# xr2206_-_FGG6.net
KiCad netlist of a schematic drawn in EAGLE
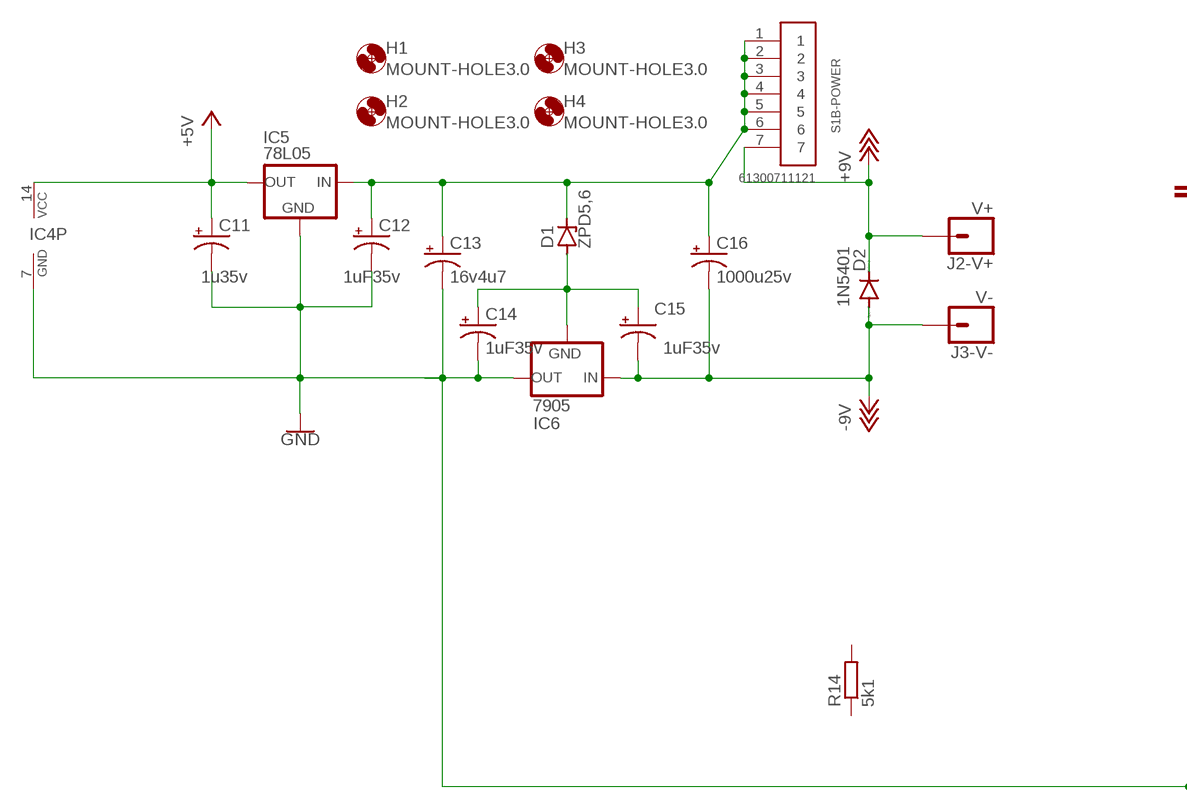
[diagram p0: schematic, sheet 1, part 1 of 2]
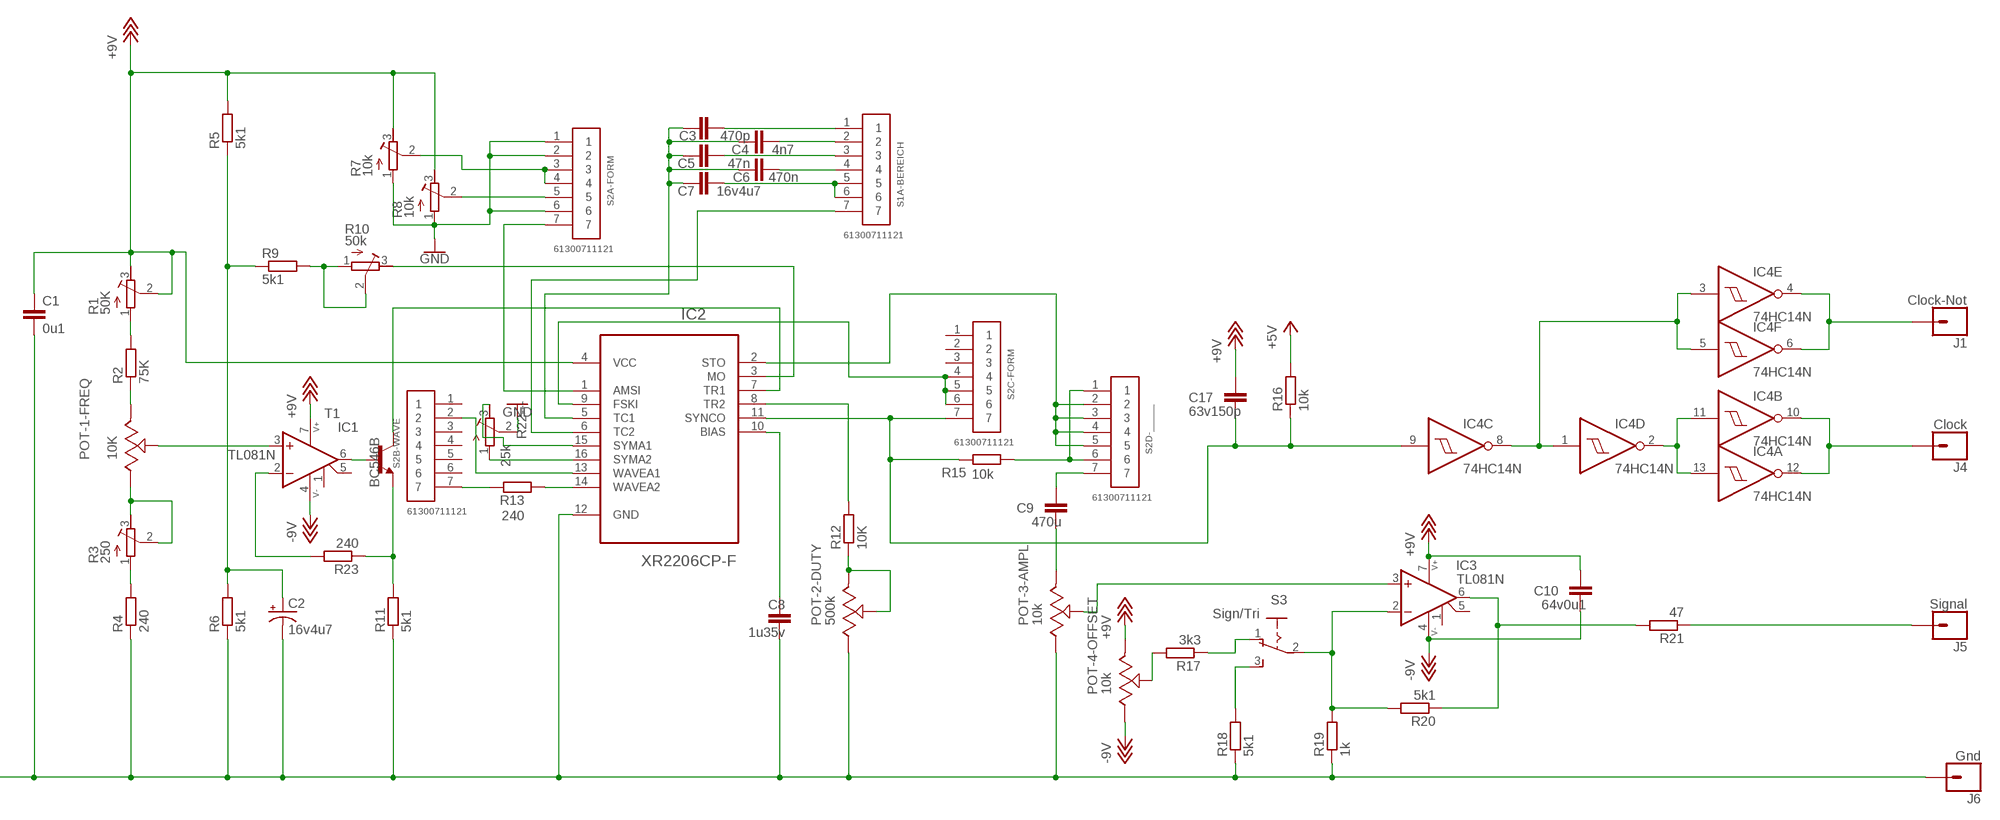
[diagram p1: schematic, sheet 1, part 2 of 2]

(export (version "E")
  (design (tool "Eeschema 10.0.6"))
  (components
    (comp (ref "C1")
      (value "0u1")
      (footprint "eagle-import:CAP-PTH-10MM")
      (libsource (lib "eagle-import") (part "10NF-PTH-10MM-10000V-1-%"))
    )
    (comp (ref "C2")
      (value "16v4u7")
      (footprint "eagle-import:CPOL-RADIAL-5MM-10MM-KIT")
      (libsource (lib "eagle-import") (part "1000UF-RADIAL-5MM-35V-20%-KIT"))
    )
    (comp (ref "C3")
      (value "470p")
      (footprint "eagle-import:CAP-PTH-10MM")
      (libsource (lib "eagle-import") (part "10NF-PTH-10MM-10000V-1-%"))
    )
    (comp (ref "C4")
      (value "4n7")
      (footprint "eagle-import:CAP-PTH-10MM")
      (libsource (lib "eagle-import") (part "10NF-PTH-10MM-10000V-1-%"))
    )
    (comp (ref "C5")
      (value "47n")
      (footprint "eagle-import:CAP-PTH-10MM")
      (libsource (lib "eagle-import") (part "10NF-PTH-10MM-10000V-1-%"))
    )
    (comp (ref "C6")
      (value "470n")
      (footprint "eagle-import:CAP-PTH-10MM")
      (libsource (lib "eagle-import") (part "10NF-PTH-10MM-10000V-1-%"))
    )
    (comp (ref "C7")
      (value "16v4u7")
      (footprint "eagle-import:CAP-PTH-10MM")
      (libsource (lib "eagle-import") (part "10NF-PTH-10MM-10000V-1-%"))
    )
    (comp (ref "C8")
      (value "1u35v")
      (footprint "eagle-import:CAP-PTH-10MM")
      (libsource (lib "eagle-import") (part "10NF-PTH-10MM-10000V-1-%"))
    )
    (comp (ref "C9")
      (value "470u")
      (footprint "eagle-import:CAP-PTH-10MM")
      (libsource (lib "eagle-import") (part "10NF-PTH-10MM-10000V-1-%"))
    )
    (comp (ref "C10")
      (value "64v0u1")
      (footprint "eagle-import:CAP-PTH-10MM")
      (libsource (lib "eagle-import") (part "10NF-PTH-10MM-10000V-1-%"))
    )
    (comp (ref "C11")
      (value "1u35v")
      (footprint "eagle-import:CPOL-RADIAL-2.5MM-5MM")
      (libsource (lib "eagle-import") (part "10UF-POLAR-RADIAL-2.5MM-25V-20%"))
    )
    (comp (ref "C12")
      (value "1uF35v")
      (footprint "eagle-import:CPOL-RADIAL-2.5MM-5MM")
      (libsource (lib "eagle-import") (part "10UF-POLAR-RADIAL-2.5MM-25V-20%"))
    )
    (comp (ref "C13")
      (value "16v4u7")
      (footprint "eagle-import:CPOL-RADIAL-2.5MM-5MM")
      (libsource (lib "eagle-import") (part "10UF-POLAR-RADIAL-2.5MM-25V-20%"))
    )
    (comp (ref "C14")
      (value "1uF35v")
      (footprint "eagle-import:CPOL-RADIAL-2.5MM-5MM")
      (libsource (lib "eagle-import") (part "10UF-POLAR-RADIAL-2.5MM-25V-20%"))
    )
    (comp (ref "C15")
      (value "1uF35v")
      (footprint "eagle-import:CPOL-RADIAL-2.5MM-5MM")
      (libsource (lib "eagle-import") (part "10UF-POLAR-RADIAL-2.5MM-25V-20%"))
    )
    (comp (ref "C16")
      (value "1000u25v")
      (footprint "eagle-import:CPOL-RADIAL-5MM-10MM-KIT")
      (libsource (lib "eagle-import") (part "1000UF-RADIAL-5MM-35V-20%-KIT"))
    )
    (comp (ref "C17")
      (value "63v150p")
      (footprint "eagle-import:CAP-PTH-10MM")
      (libsource (lib "eagle-import") (part "10NF-PTH-10MM-10000V-1-%"))
    )
    (comp (ref "D1")
      (value "ZPD5,6")
      (footprint "eagle-import:C1702-15")
      (libsource (lib "eagle-import") (part "1N5333"))
    )
    (comp (ref "D2")
      (value "1N5401")
      (footprint "eagle-import:DO201-15")
      (libsource (lib "eagle-import") (part "1N5400"))
    )
    (comp (ref "H1")
      (value "MOUNT-HOLE3.0")
      (footprint "eagle-import:3,0")
      (libsource (lib "eagle-import") (part "MOUNT-HOLE3.0"))
    )
    (comp (ref "H2")
      (value "MOUNT-HOLE3.0")
      (footprint "eagle-import:3,0")
      (libsource (lib "eagle-import") (part "MOUNT-HOLE3.0"))
    )
    (comp (ref "H3")
      (value "MOUNT-HOLE3.0")
      (footprint "eagle-import:3,0")
      (libsource (lib "eagle-import") (part "MOUNT-HOLE3.0"))
    )
    (comp (ref "H4")
      (value "MOUNT-HOLE3.0")
      (footprint "eagle-import:3,0")
      (libsource (lib "eagle-import") (part "MOUNT-HOLE3.0"))
    )
    (comp (ref "IC1")
      (value "TL081N")
      (footprint "eagle-import:DIL08")
      (libsource (lib "eagle-import") (part "TL081N"))
    )
    (comp (ref "IC2")
      (value "XR2206CP-F")
      (footprint "eagle-import:DIP254P762X533-16")
      (fields (field (name "MF") "MaxLinear, Inc."))
      (libsource (lib "eagle-import") (part "XR2206CP-F"))
    )
    (comp (ref "IC3")
      (value "TL081N")
      (footprint "eagle-import:DIL08")
      (libsource (lib "eagle-import") (part "TL081N"))
    )
    (comp (ref "IC4")
      (value "74HC14N")
      (footprint "eagle-import:DIL14")
      (libsource (lib "eagle-import") (part "7414NHC"))
    )
    (comp (ref "IC5")
      (value "78L05")
      (footprint "eagle-import:78XXL")
      (libsource (lib "eagle-import") (part "78XXL"))
    )
    (comp (ref "IC6")
      (value "7905")
      (footprint "eagle-import:79XXL")
      (libsource (lib "eagle-import") (part "79XXL"))
    )
    (comp (ref "J1")
      (value "Clock-Not")
      (footprint "eagle-import:1X01")
      (libsource (lib "eagle-import") (part "CONN_01"))
    )
    (comp (ref "J2-V+")
      (value "V+")
      (footprint "eagle-import:1X01")
      (libsource (lib "eagle-import") (part "CONN_01"))
    )
    (comp (ref "J3-V-")
      (value "V-")
      (footprint "eagle-import:1X01")
      (libsource (lib "eagle-import") (part "CONN_01"))
    )
    (comp (ref "J4")
      (value "Clock")
      (footprint "eagle-import:1X01")
      (libsource (lib "eagle-import") (part "CONN_01"))
    )
    (comp (ref "J5")
      (value "Signal")
      (footprint "eagle-import:1X01")
      (libsource (lib "eagle-import") (part "CONN_01"))
    )
    (comp (ref "J6")
      (value "Gnd")
      (footprint "eagle-import:1X01")
      (libsource (lib "eagle-import") (part "CONN_01"))
    )
    (comp (ref "POT-1-FREQ")
      (value "10K")
      (footprint "eagle-import:3310C-001-503L")
      (fields
        (field (name "DIGIKEY_PARTNO") "3310C-001-503L-ND")
        (field (name "MANUFACTURER") "Bourns Inc.")
        (field (name "MPN") "3310C-001-503L")
        (field (name "CREATED_BY") "PCBLayout.com")
      )
      (libsource (lib "eagle-import") (part "3310C-001-503L"))
    )
    (comp (ref "POT-2-DUTY")
      (value "500k")
      (footprint "eagle-import:3310C-001-503L")
      (fields
        (field (name "DIGIKEY_PARTNO") "3310C-001-503L-ND")
        (field (name "MANUFACTURER") "Bourns Inc.")
        (field (name "MPN") "3310C-001-503L")
        (field (name "CREATED_BY") "PCBLayout.com")
      )
      (libsource (lib "eagle-import") (part "3310C-001-503L"))
    )
    (comp (ref "POT-3-AMPL")
      (value "10k")
      (footprint "eagle-import:3310C-001-503L")
      (fields
        (field (name "DIGIKEY_PARTNO") "3310C-001-503L-ND")
        (field (name "MANUFACTURER") "Bourns Inc.")
        (field (name "MPN") "3310C-001-503L")
        (field (name "CREATED_BY") "PCBLayout.com")
      )
      (libsource (lib "eagle-import") (part "3310C-001-503L"))
    )
    (comp (ref "POT-4-OFFSET")
      (value "10k")
      (footprint "eagle-import:3310C-001-503L")
      (fields
        (field (name "DIGIKEY_PARTNO") "3310C-001-503L-ND")
        (field (name "MANUFACTURER") "Bourns Inc.")
        (field (name "MPN") "3310C-001-503L")
        (field (name "CREATED_BY") "PCBLayout.com")
      )
      (libsource (lib "eagle-import") (part "3310C-001-503L"))
    )
    (comp (ref "R1")
      (value "50K")
      (footprint "eagle-import:RTRIM64W")
      (libsource (lib "eagle-import") (part "R-TRIMM64W"))
    )
    (comp (ref "R2")
      (value "75K")
      (footprint "eagle-import:0207_12")
      (libsource (lib "eagle-import") (part "R-EU_0207/12"))
    )
    (comp (ref "R3")
      (value "250")
      (footprint "eagle-import:RTRIM64W")
      (libsource (lib "eagle-import") (part "R-TRIMM64W"))
    )
    (comp (ref "R4")
      (value "240")
      (footprint "eagle-import:0207_7")
      (libsource (lib "eagle-import") (part "R-EU_0207/7"))
    )
    (comp (ref "R5")
      (value "5k1")
      (footprint "eagle-import:0207_7")
      (libsource (lib "eagle-import") (part "R-EU_0207/7"))
    )
    (comp (ref "R6")
      (value "5k1")
      (footprint "eagle-import:0207_7")
      (libsource (lib "eagle-import") (part "R-EU_0207/7"))
    )
    (comp (ref "R7")
      (value "10k")
      (footprint "eagle-import:RTRIM64W")
      (libsource (lib "eagle-import") (part "R-TRIMM64W"))
    )
    (comp (ref "R8")
      (value "10k")
      (footprint "eagle-import:RTRIM64W")
      (libsource (lib "eagle-import") (part "R-TRIMM64W"))
    )
    (comp (ref "R9")
      (value "5k1")
      (footprint "eagle-import:0207_12")
      (libsource (lib "eagle-import") (part "R-EU_0207/12"))
    )
    (comp (ref "R10")
      (value "50k")
      (footprint "eagle-import:RTRIM64W")
      (libsource (lib "eagle-import") (part "R-TRIMM64W"))
    )
    (comp (ref "R11")
      (value "5k1")
      (footprint "eagle-import:0207_7")
      (libsource (lib "eagle-import") (part "R-EU_0207/7"))
    )
    (comp (ref "R12")
      (value "10K")
      (footprint "eagle-import:0207_12")
      (libsource (lib "eagle-import") (part "R-EU_0207/12"))
    )
    (comp (ref "R13")
      (value "240")
      (footprint "eagle-import:0207_7")
      (libsource (lib "eagle-import") (part "R-EU_0207/7"))
    )
    (comp (ref "R14")
      (value "5k1")
      (footprint "eagle-import:0207_7")
      (libsource (lib "eagle-import") (part "R-EU_0207/7"))
    )
    (comp (ref "R15")
      (value "10k")
      (footprint "eagle-import:0207_7")
      (libsource (lib "eagle-import") (part "R-EU_0207/7"))
    )
    (comp (ref "R16")
      (value "10k")
      (footprint "eagle-import:0207_7")
      (libsource (lib "eagle-import") (part "R-EU_0207/7"))
    )
    (comp (ref "R17")
      (value "3k3")
      (footprint "eagle-import:0207_12")
      (libsource (lib "eagle-import") (part "R-EU_0207/12"))
    )
    (comp (ref "R18")
      (value "5k1")
      (footprint "eagle-import:0207_7")
      (libsource (lib "eagle-import") (part "R-EU_0207/7"))
    )
    (comp (ref "R19")
      (value "1k")
      (footprint "eagle-import:0207_7")
      (libsource (lib "eagle-import") (part "R-EU_0207/7"))
    )
    (comp (ref "R20")
      (value "5k1")
      (footprint "eagle-import:0207_7")
      (libsource (lib "eagle-import") (part "R-EU_0207/7"))
    )
    (comp (ref "R21")
      (value "47")
      (footprint "eagle-import:0207_7")
      (libsource (lib "eagle-import") (part "R-EU_0207/7"))
    )
    (comp (ref "R22---")
      (value "25k")
      (footprint "eagle-import:RTRIM64W")
      (libsource (lib "eagle-import") (part "R-TRIMM64W"))
    )
    (comp (ref "R23")
      (value "240")
      (footprint "eagle-import:0207_12")
      (libsource (lib "eagle-import") (part "R-EU_0207/12"))
    )
    (comp (ref "S1A-BEREICH")
      (value "61300711121")
      (footprint "eagle-import:61300711121")
      (fields
        (field (name "DIGI_KEY_PART_NUMBER") "732-5320-ND")
        (field (name "MANUFACTURER") "Wurth Electronics Inc.")
        (field (name "CREATED_BY") "PCBLayout.com")
      )
      (libsource (lib "eagle-import") (part "61300711121"))
    )
    (comp (ref "S1B-POWER")
      (value "61300711121")
      (footprint "eagle-import:61300711121")
      (fields
        (field (name "DIGI_KEY_PART_NUMBER") "732-5320-ND")
        (field (name "MANUFACTURER") "Wurth Electronics Inc.")
        (field (name "CREATED_BY") "PCBLayout.com")
      )
      (libsource (lib "eagle-import") (part "61300711121"))
    )
    (comp (ref "S2A-FORM")
      (value "61300711121")
      (footprint "eagle-import:61300711121")
      (fields
        (field (name "DIGI_KEY_PART_NUMBER") "732-5320-ND")
        (field (name "MANUFACTURER") "Wurth Electronics Inc.")
        (field (name "CREATED_BY") "PCBLayout.com")
      )
      (libsource (lib "eagle-import") (part "61300711121"))
    )
    (comp (ref "S2B-WAVE")
      (value "61300711121")
      (footprint "eagle-import:61300711121")
      (fields
        (field (name "DIGI_KEY_PART_NUMBER") "732-5320-ND")
        (field (name "MANUFACTURER") "Wurth Electronics Inc.")
        (field (name "CREATED_BY") "PCBLayout.com")
      )
      (libsource (lib "eagle-import") (part "61300711121"))
    )
    (comp (ref "S2C-FORM")
      (value "61300711121")
      (footprint "eagle-import:61300711121")
      (fields
        (field (name "DIGI_KEY_PART_NUMBER") "732-5320-ND")
        (field (name "MANUFACTURER") "Wurth Electronics Inc.")
        (field (name "CREATED_BY") "PCBLayout.com")
      )
      (libsource (lib "eagle-import") (part "61300711121"))
    )
    (comp (ref "S2D-_____")
      (value "61300711121")
      (footprint "eagle-import:61300711121")
      (fields
        (field (name "DIGI_KEY_PART_NUMBER") "732-5320-ND")
        (field (name "MANUFACTURER") "Wurth Electronics Inc.")
        (field (name "CREATED_BY") "PCBLayout.com")
      )
      (libsource (lib "eagle-import") (part "61300711121"))
    )
    (comp (ref "S3")
      (value "Sign/Tri")
      (footprint "eagle-import:255SB")
      (libsource (lib "eagle-import") (part "255SB"))
    )
    (comp (ref "T1")
      (value "BC546B")
      (footprint "eagle-import:TO92-EBC")
      (libsource (lib "eagle-import") (part "BC546B"))
    )
  )
  (nets
    (net (code "1") (name "+5V") (class "Default")
      (node (ref "C11") (pin "1") (pinfunction "+_1") (pintype "passive"))
      (node (ref "IC4") (pin "14") (pinfunction "VCC_14") (pintype "power_in"))
      (node (ref "IC5") (pin "OUT") (pinfunction "OUT_OUT") (pintype "passive"))
      (node (ref "R16") (pin "2") (pinfunction "2_2") (pintype "passive"))
    )
    (net (code "2") (name "+9V") (class "Default")
      (node (ref "C1") (pin "1") (pinfunction "1_1") (pintype "passive"))
      (node (ref "C10") (pin "2") (pinfunction "2_2") (pintype "passive"))
      (node (ref "C17") (pin "2") (pinfunction "2_2") (pintype "passive"))
      (node (ref "D2") (pin "C") (pinfunction "C_C") (pintype "passive"))
      (node (ref "IC1") (pin "7") (pinfunction "V+_7") (pintype "power_in"))
      (node (ref "IC2") (pin "4") (pinfunction "VCC_4") (pintype "power_in"))
      (node (ref "IC3") (pin "7") (pinfunction "V+_7") (pintype "power_in"))
      (node (ref "J2-V+") (pin "1") (pinfunction "1_1") (pintype "passive"))
      (node (ref "POT-4-OFFSET") (pin "1") (pinfunction "1_1") (pintype "passive"))
      (node (ref "R1") (pin "2") (pinfunction "S_2") (pintype "passive"))
      (node (ref "R1") (pin "3") (pinfunction "E_3") (pintype "passive"))
      (node (ref "R5") (pin "2") (pinfunction "2_2") (pintype "passive"))
      (node (ref "R7") (pin "3") (pinfunction "E_3") (pintype "passive"))
      (node (ref "R8") (pin "3") (pinfunction "E_3") (pintype "passive"))
      (node (ref "S1B-POWER") (pin "7") (pinfunction "7_7") (pintype "passive"))
    )
    (net (code "3") (name "-9V") (class "Default")
      (node (ref "C10") (pin "1") (pinfunction "1_1") (pintype "passive"))
      (node (ref "C15") (pin "2") (pinfunction "-_2") (pintype "passive"))
      (node (ref "C16") (pin "-") (pinfunction "-_-") (pintype "passive"))
      (node (ref "D2") (pin "A") (pinfunction "A_A") (pintype "passive"))
      (node (ref "IC1") (pin "4") (pinfunction "V-_4") (pintype "power_in"))
      (node (ref "IC3") (pin "4") (pinfunction "V-_4") (pintype "power_in"))
      (node (ref "IC6") (pin "IN") (pinfunction "IN_IN") (pintype "input"))
      (node (ref "J3-V-") (pin "1") (pinfunction "1_1") (pintype "passive"))
      (node (ref "POT-4-OFFSET") (pin "3") (pinfunction "3_3") (pintype "passive"))
    )
    (net (code "4") (name "GND") (class "Default")
      (node (ref "C1") (pin "2") (pinfunction "2_2") (pintype "passive"))
      (node (ref "C11") (pin "2") (pinfunction "-_2") (pintype "passive"))
      (node (ref "C12") (pin "2") (pinfunction "-_2") (pintype "passive"))
      (node (ref "C13") (pin "2") (pinfunction "-_2") (pintype "passive"))
      (node (ref "C14") (pin "2") (pinfunction "-_2") (pintype "passive"))
      (node (ref "C2") (pin "-") (pinfunction "-_-") (pintype "passive"))
      (node (ref "C8") (pin "1") (pinfunction "1_1") (pintype "passive"))
      (node (ref "IC2") (pin "12") (pinfunction "GND_12") (pintype "passive"))
      (node (ref "IC4") (pin "7") (pinfunction "GND_7") (pintype "power_in"))
      (node (ref "IC5") (pin "GND") (pinfunction "GND_GND") (pintype "input"))
      (node (ref "IC6") (pin "OUT") (pinfunction "OUT_OUT") (pintype "passive"))
      (node (ref "J6") (pin "1") (pinfunction "1_1") (pintype "passive"))
      (node (ref "POT-2-DUTY") (pin "3") (pinfunction "3_3") (pintype "passive"))
      (node (ref "POT-3-AMPL") (pin "3") (pinfunction "3_3") (pintype "passive"))
      (node (ref "R11") (pin "1") (pinfunction "1_1") (pintype "passive"))
      (node (ref "R18") (pin "1") (pinfunction "1_1") (pintype "passive"))
      (node (ref "R19") (pin "1") (pinfunction "1_1") (pintype "passive"))
      (node (ref "R22---") (pin "2") (pinfunction "S_2") (pintype "passive"))
      (node (ref "R4") (pin "1") (pinfunction "1_1") (pintype "passive"))
      (node (ref "R6") (pin "1") (pinfunction "1_1") (pintype "passive"))
      (node (ref "R7") (pin "1") (pinfunction "A_1") (pintype "passive"))
      (node (ref "R8") (pin "1") (pinfunction "A_1") (pintype "passive"))
      (node (ref "S2A-FORM") (pin "1") (pinfunction "1_1") (pintype "passive"))
      (node (ref "S2A-FORM") (pin "2") (pinfunction "2_2") (pintype "passive"))
      (node (ref "S2A-FORM") (pin "6") (pinfunction "6_6") (pintype "passive"))
    )
    (net (code "5") (name "Net-(C2-Pad+)") (class "Default")
      (node (ref "C2") (pin "+") (pinfunction "+_+") (pintype "passive"))
      (node (ref "R5") (pin "1") (pinfunction "1_1") (pintype "passive"))
      (node (ref "R6") (pin "2") (pinfunction "2_2") (pintype "passive"))
      (node (ref "R9") (pin "1") (pinfunction "1_1") (pintype "passive"))
    )
    (net (code "6") (name "Net-(C3-Pad2)") (class "Default")
      (node (ref "C3") (pin "2") (pinfunction "2_2") (pintype "passive"))
      (node (ref "S1A-BEREICH") (pin "1") (pinfunction "1_1") (pintype "passive"))
    )
    (net (code "7") (name "Net-(C4-Pad2)") (class "Default")
      (node (ref "C4") (pin "2") (pinfunction "2_2") (pintype "passive"))
      (node (ref "S1A-BEREICH") (pin "2") (pinfunction "2_2") (pintype "passive"))
    )
    (net (code "8") (name "Net-(C5-Pad2)") (class "Default")
      (node (ref "C5") (pin "2") (pinfunction "2_2") (pintype "passive"))
      (node (ref "S1A-BEREICH") (pin "3") (pinfunction "3_3") (pintype "passive"))
    )
    (net (code "9") (name "Net-(C6-Pad2)") (class "Default")
      (node (ref "C6") (pin "2") (pinfunction "2_2") (pintype "passive"))
      (node (ref "S1A-BEREICH") (pin "4") (pinfunction "4_4") (pintype "passive"))
    )
    (net (code "10") (name "Net-(C7-Pad2)") (class "Default")
      (node (ref "C7") (pin "2") (pinfunction "2_2") (pintype "passive"))
      (node (ref "S1A-BEREICH") (pin "5") (pinfunction "5_5") (pintype "passive"))
      (node (ref "S1A-BEREICH") (pin "6") (pinfunction "6_6") (pintype "passive"))
    )
    (net (code "11") (name "Net-(C9-Pad1)") (class "Default")
      (node (ref "C9") (pin "1") (pinfunction "1_1") (pintype "passive"))
      (node (ref "POT-3-AMPL") (pin "1") (pinfunction "1_1") (pintype "passive"))
    )
    (net (code "12") (name "Net-(C9-Pad2)") (class "Default")
      (node (ref "C9") (pin "2") (pinfunction "2_2") (pintype "passive"))
      (node (ref "S2D-_____") (pin "7") (pinfunction "7_7") (pintype "passive"))
    )
    (net (code "13") (name "Net-(C12-+)") (class "Default")
      (node (ref "C12") (pin "1") (pinfunction "+_1") (pintype "passive"))
      (node (ref "C13") (pin "1") (pinfunction "+_1") (pintype "passive"))
      (node (ref "C16") (pin "+") (pinfunction "+_+") (pintype "passive"))
      (node (ref "D1") (pin "C") (pinfunction "C_C") (pintype "passive"))
      (node (ref "IC5") (pin "IN") (pinfunction "IN_IN") (pintype "input"))
      (node (ref "S1B-POWER") (pin "1") (pinfunction "1_1") (pintype "passive"))
      (node (ref "S1B-POWER") (pin "2") (pinfunction "2_2") (pintype "passive"))
      (node (ref "S1B-POWER") (pin "3") (pinfunction "3_3") (pintype "passive"))
      (node (ref "S1B-POWER") (pin "4") (pinfunction "4_4") (pintype "passive"))
      (node (ref "S1B-POWER") (pin "5") (pinfunction "5_5") (pintype "passive"))
      (node (ref "S1B-POWER") (pin "6") (pinfunction "6_6") (pintype "passive"))
    )
    (net (code "14") (name "Net-(C14-+)") (class "Default")
      (node (ref "C14") (pin "1") (pinfunction "+_1") (pintype "passive"))
      (node (ref "C15") (pin "1") (pinfunction "+_1") (pintype "passive"))
      (node (ref "D1") (pin "A") (pinfunction "A_A") (pintype "passive"))
      (node (ref "IC6") (pin "GND") (pinfunction "GND_GND") (pintype "input"))
    )
    (net (code "15") (name "Net-(IC1B-+IN)") (class "Default")
      (node (ref "IC1") (pin "3") (pinfunction "+IN_3") (pintype "input"))
      (node (ref "POT-1-FREQ") (pin "2") (pinfunction "2_2") (pintype "passive"))
    )
    (net (code "16") (name "Net-(IC1B--IN)") (class "Default")
      (node (ref "IC1") (pin "2") (pinfunction "-IN_2") (pintype "input"))
      (node (ref "R23") (pin "2") (pinfunction "2_2") (pintype "passive"))
    )
    (net (code "17") (name "Net-(IC1B-OUT)") (class "Default")
      (node (ref "IC1") (pin "6") (pinfunction "OUT_6") (pintype "output"))
      (node (ref "T1") (pin "B") (pinfunction "B_B") (pintype "passive"))
    )
    (net (code "18") (name "Net-(IC2-AMSI)") (class "Default")
      (node (ref "IC2") (pin "1") (pinfunction "AMSI_1") (pintype "input"))
      (node (ref "S2A-FORM") (pin "7") (pinfunction "7_7") (pintype "passive"))
    )
    (net (code "19") (name "Net-(IC2-BIAS)") (class "Default")
      (node (ref "C8") (pin "2") (pinfunction "2_2") (pintype "passive"))
      (node (ref "IC2") (pin "10") (pinfunction "BIAS_10") (pintype "output"))
    )
    (net (code "20") (name "Net-(IC2-FSKI)") (class "Default")
      (node (ref "IC2") (pin "9") (pinfunction "FSKI_9") (pintype "input"))
      (node (ref "S2C-FORM") (pin "4") (pinfunction "4_4") (pintype "passive"))
      (node (ref "S2C-FORM") (pin "5") (pinfunction "5_5") (pintype "passive"))
      (node (ref "S2C-FORM") (pin "6") (pinfunction "6_6") (pintype "passive"))
    )
    (net (code "21") (name "Net-(IC2-MO)") (class "Default")
      (node (ref "IC2") (pin "3") (pinfunction "MO_3") (pintype "output"))
      (node (ref "R10") (pin "3") (pinfunction "E_3") (pintype "passive"))
    )
    (net (code "22") (name "Net-(IC2-STO)") (class "Default")
      (node (ref "IC2") (pin "2") (pinfunction "STO_2") (pintype "output"))
      (node (ref "S2D-_____") (pin "2") (pinfunction "2_2") (pintype "passive"))
      (node (ref "S2D-_____") (pin "3") (pinfunction "3_3") (pintype "passive"))
      (node (ref "S2D-_____") (pin "4") (pinfunction "4_4") (pintype "passive"))
      (node (ref "S2D-_____") (pin "5") (pinfunction "5_5") (pintype "passive"))
    )
    (net (code "23") (name "Net-(IC2-SYMA1)") (class "Default")
      (node (ref "IC2") (pin "15") (pinfunction "SYMA1_15") (pintype "input"))
      (node (ref "R22---") (pin "3") (pinfunction "E_3") (pintype "passive"))
    )
    (net (code "24") (name "Net-(IC2-SYMA2)") (class "Default")
      (node (ref "IC2") (pin "16") (pinfunction "SYMA2_16") (pintype "input"))
      (node (ref "R22---") (pin "1") (pinfunction "A_1") (pintype "passive"))
    )
    (net (code "25") (name "Net-(IC2-SYNCO)") (class "Default")
      (node (ref "C17") (pin "1") (pinfunction "1_1") (pintype "passive"))
      (node (ref "IC2") (pin "11") (pinfunction "SYNCO_11") (pintype "output"))
      (node (ref "IC4") (pin "9") (pinfunction "I_9") (pintype "input"))
      (node (ref "R15") (pin "2") (pinfunction "2_2") (pintype "passive"))
      (node (ref "R16") (pin "1") (pinfunction "1_1") (pintype "passive"))
      (node (ref "S2C-FORM") (pin "7") (pinfunction "7_7") (pintype "passive"))
    )
    (net (code "26") (name "Net-(IC2-TC1)") (class "Default")
      (node (ref "C3") (pin "1") (pinfunction "1_1") (pintype "passive"))
      (node (ref "C4") (pin "1") (pinfunction "1_1") (pintype "passive"))
      (node (ref "C5") (pin "1") (pinfunction "1_1") (pintype "passive"))
      (node (ref "C6") (pin "1") (pinfunction "1_1") (pintype "passive"))
      (node (ref "C7") (pin "1") (pinfunction "1_1") (pintype "passive"))
      (node (ref "IC2") (pin "5") (pinfunction "TC1_5") (pintype "input"))
    )
    (net (code "27") (name "Net-(IC2-TC2)") (class "Default")
      (node (ref "IC2") (pin "6") (pinfunction "TC2_6") (pintype "input"))
      (node (ref "S1A-BEREICH") (pin "7") (pinfunction "7_7") (pintype "passive"))
    )
    (net (code "28") (name "Net-(IC2-TR1)") (class "Default")
      (node (ref "IC2") (pin "7") (pinfunction "TR1_7") (pintype "output"))
      (node (ref "T1") (pin "C") (pinfunction "C_C") (pintype "passive"))
    )
    (net (code "29") (name "Net-(IC2-TR2)") (class "Default")
      (node (ref "IC2") (pin "8") (pinfunction "TR2_8") (pintype "output"))
      (node (ref "R12") (pin "2") (pinfunction "2_2") (pintype "passive"))
    )
    (net (code "30") (name "Net-(IC2-WAVEA1)") (class "Default")
      (node (ref "IC2") (pin "13") (pinfunction "WAVEA1_13") (pintype "input"))
      (node (ref "S2B-WAVE") (pin "2") (pinfunction "2_2") (pintype "passive"))
    )
    (net (code "31") (name "Net-(IC2-WAVEA2)") (class "Default")
      (node (ref "IC2") (pin "14") (pinfunction "WAVEA2_14") (pintype "input"))
      (node (ref "R13") (pin "1") (pinfunction "1_1") (pintype "passive"))
    )
    (net (code "32") (name "Net-(IC3B-+IN)") (class "Default")
      (node (ref "IC3") (pin "3") (pinfunction "+IN_3") (pintype "input"))
      (node (ref "POT-3-AMPL") (pin "2") (pinfunction "2_2") (pintype "passive"))
    )
    (net (code "33") (name "Net-(IC3B--IN)") (class "Default")
      (node (ref "IC3") (pin "2") (pinfunction "-IN_2") (pintype "input"))
      (node (ref "R19") (pin "2") (pinfunction "2_2") (pintype "passive"))
      (node (ref "R20") (pin "2") (pinfunction "2_2") (pintype "passive"))
      (node (ref "S3") (pin "2") (pinfunction "P_2") (pintype "passive"))
    )
    (net (code "34") (name "Net-(IC3B-OUT)") (class "Default")
      (node (ref "IC3") (pin "6") (pinfunction "OUT_6") (pintype "output"))
      (node (ref "R20") (pin "1") (pinfunction "1_1") (pintype "passive"))
      (node (ref "R21") (pin "2") (pinfunction "2_2") (pintype "passive"))
    )
    (net (code "35") (name "Net-(IC4A-I)") (class "Default")
      (node (ref "IC4") (pin "11") (pinfunction "I_11") (pintype "input"))
      (node (ref "IC4") (pin "13") (pinfunction "I_13") (pintype "input"))
      (node (ref "IC4") (pin "2") (pinfunction "O_2") (pintype "output"))
    )
    (net (code "36") (name "Net-(IC4A-O)") (class "Default")
      (node (ref "IC4") (pin "10") (pinfunction "O_10") (pintype "output"))
      (node (ref "IC4") (pin "12") (pinfunction "O_12") (pintype "output"))
      (node (ref "J4") (pin "1") (pinfunction "1_1") (pintype "passive"))
    )
    (net (code "37") (name "Net-(IC4C-O)") (class "Default")
      (node (ref "IC4") (pin "1") (pinfunction "I_1") (pintype "input"))
      (node (ref "IC4") (pin "3") (pinfunction "I_3") (pintype "input"))
      (node (ref "IC4") (pin "5") (pinfunction "I_5") (pintype "input"))
      (node (ref "IC4") (pin "8") (pinfunction "O_8") (pintype "output"))
    )
    (net (code "38") (name "Net-(IC4E-O)") (class "Default")
      (node (ref "IC4") (pin "4") (pinfunction "O_4") (pintype "output"))
      (node (ref "IC4") (pin "6") (pinfunction "O_6") (pintype "output"))
      (node (ref "J1") (pin "1") (pinfunction "1_1") (pintype "passive"))
    )
    (net (code "39") (name "Net-(J5-Pad1)") (class "Default")
      (node (ref "J5") (pin "1") (pinfunction "1_1") (pintype "passive"))
      (node (ref "R21") (pin "1") (pinfunction "1_1") (pintype "passive"))
    )
    (net (code "40") (name "Net-(POT-1-FREQ-Pad1)") (class "Default")
      (node (ref "POT-1-FREQ") (pin "1") (pinfunction "1_1") (pintype "passive"))
      (node (ref "R2") (pin "1") (pinfunction "1_1") (pintype "passive"))
    )
    (net (code "41") (name "Net-(POT-2-DUTY-Pad1)") (class "Default")
      (node (ref "POT-2-DUTY") (pin "1") (pinfunction "1_1") (pintype "passive"))
      (node (ref "POT-2-DUTY") (pin "2") (pinfunction "2_2") (pintype "passive"))
      (node (ref "R12") (pin "1") (pinfunction "1_1") (pintype "passive"))
    )
    (net (code "42") (name "Net-(POT-4-OFFSET-Pad2)") (class "Default")
      (node (ref "POT-4-OFFSET") (pin "2") (pinfunction "2_2") (pintype "passive"))
      (node (ref "R17") (pin "2") (pinfunction "2_2") (pintype "passive"))
    )
    (net (code "43") (name "Net-(R1-A)") (class "Default")
      (node (ref "R1") (pin "1") (pinfunction "A_1") (pintype "passive"))
      (node (ref "R2") (pin "2") (pinfunction "2_2") (pintype "passive"))
    )
    (net (code "44") (name "Net-(R3-A)") (class "Default")
      (node (ref "R3") (pin "1") (pinfunction "A_1") (pintype "passive"))
      (node (ref "R4") (pin "2") (pinfunction "2_2") (pintype "passive"))
    )
    (net (code "45") (name "Net-(R3-E)") (class "Default")
      (node (ref "POT-1-FREQ") (pin "3") (pinfunction "3_3") (pintype "passive"))
      (node (ref "R3") (pin "2") (pinfunction "S_2") (pintype "passive"))
      (node (ref "R3") (pin "3") (pinfunction "E_3") (pintype "passive"))
    )
    (net (code "46") (name "Net-(R7-S)") (class "Default")
      (node (ref "R7") (pin "2") (pinfunction "S_2") (pintype "passive"))
      (node (ref "S2A-FORM") (pin "3") (pinfunction "3_3") (pintype "passive"))
      (node (ref "S2A-FORM") (pin "4") (pinfunction "4_4") (pintype "passive"))
    )
    (net (code "47") (name "Net-(R8-S)") (class "Default")
      (node (ref "R8") (pin "2") (pinfunction "S_2") (pintype "passive"))
      (node (ref "S2A-FORM") (pin "5") (pinfunction "5_5") (pintype "passive"))
    )
    (net (code "48") (name "Net-(R10-A)") (class "Default")
      (node (ref "R10") (pin "1") (pinfunction "A_1") (pintype "passive"))
      (node (ref "R10") (pin "2") (pinfunction "S_2") (pintype "passive"))
      (node (ref "R9") (pin "2") (pinfunction "2_2") (pintype "passive"))
    )
    (net (code "49") (name "Net-(R11-Pad2)") (class "Default")
      (node (ref "R11") (pin "2") (pinfunction "2_2") (pintype "passive"))
      (node (ref "R23") (pin "1") (pinfunction "1_1") (pintype "passive"))
      (node (ref "T1") (pin "E") (pinfunction "E_E") (pintype "passive"))
    )
    (net (code "50") (name "Net-(R13-Pad2)") (class "Default")
      (node (ref "R13") (pin "2") (pinfunction "2_2") (pintype "passive"))
      (node (ref "S2B-WAVE") (pin "7") (pinfunction "7_7") (pintype "passive"))
    )
    (net (code "51") (name "Net-(R15-Pad1)") (class "Default")
      (node (ref "R15") (pin "1") (pinfunction "1_1") (pintype "passive"))
      (node (ref "S2D-_____") (pin "1") (pinfunction "1_1") (pintype "passive"))
      (node (ref "S2D-_____") (pin "6") (pinfunction "6_6") (pintype "passive"))
    )
    (net (code "52") (name "Net-(S3-O)") (class "Default")
      (node (ref "R17") (pin "1") (pinfunction "1_1") (pintype "passive"))
      (node (ref "S3") (pin "1") (pinfunction "O_1") (pintype "passive"))
    )
    (net (code "53") (name "Net-(S3-S)") (class "Default")
      (node (ref "R18") (pin "2") (pinfunction "2_2") (pintype "passive"))
      (node (ref "S3") (pin "3") (pinfunction "S_3") (pintype "passive"))
    )
    (net (code "54") (name "unconnected-(IC1A-NULL1-Pad1)") (class "Default")
      (node (ref "IC1") (pin "1") (pinfunction "NULL1_1") (pintype "passive"))
    )
    (net (code "55") (name "unconnected-(IC1A-NULL2-Pad5)") (class "Default")
      (node (ref "IC1") (pin "5") (pinfunction "NULL2_5") (pintype "passive"))
    )
    (net (code "56") (name "unconnected-(IC3A-NULL1-Pad1)") (class "Default")
      (node (ref "IC3") (pin "1") (pinfunction "NULL1_1") (pintype "passive"))
    )
    (net (code "57") (name "unconnected-(IC3A-NULL2-Pad5)") (class "Default")
      (node (ref "IC3") (pin "5") (pinfunction "NULL2_5") (pintype "passive"))
    )
    (net (code "58") (name "unconnected-(R14-Pad1)") (class "Default")
      (node (ref "R14") (pin "1") (pinfunction "1_1") (pintype "passive"))
    )
    (net (code "59") (name "unconnected-(R14-Pad2)") (class "Default")
      (node (ref "R14") (pin "2") (pinfunction "2_2") (pintype "passive"))
    )
    (net (code "60") (name "unconnected-(S2B-WAVE-Pad1)") (class "Default")
      (node (ref "S2B-WAVE") (pin "1") (pinfunction "1_1") (pintype "passive"))
    )
    (net (code "61") (name "unconnected-(S2B-WAVE-Pad3)") (class "Default")
      (node (ref "S2B-WAVE") (pin "3") (pinfunction "3_3") (pintype "passive"))
    )
    (net (code "62") (name "unconnected-(S2B-WAVE-Pad4)") (class "Default")
      (node (ref "S2B-WAVE") (pin "4") (pinfunction "4_4") (pintype "passive"))
    )
    (net (code "63") (name "unconnected-(S2B-WAVE-Pad5)") (class "Default")
      (node (ref "S2B-WAVE") (pin "5") (pinfunction "5_5") (pintype "passive"))
    )
    (net (code "64") (name "unconnected-(S2B-WAVE-Pad6)") (class "Default")
      (node (ref "S2B-WAVE") (pin "6") (pinfunction "6_6") (pintype "passive"))
    )
    (net (code "65") (name "unconnected-(S2C-FORM-Pad1)") (class "Default")
      (node (ref "S2C-FORM") (pin "1") (pinfunction "1_1") (pintype "passive"))
    )
    (net (code "66") (name "unconnected-(S2C-FORM-Pad2)") (class "Default")
      (node (ref "S2C-FORM") (pin "2") (pinfunction "2_2") (pintype "passive"))
    )
    (net (code "67") (name "unconnected-(S2C-FORM-Pad3)") (class "Default")
      (node (ref "S2C-FORM") (pin "3") (pinfunction "3_3") (pintype "passive"))
    )
  )
)
